# main.net
KiCad netlist of a schematic drawn in EAGLE
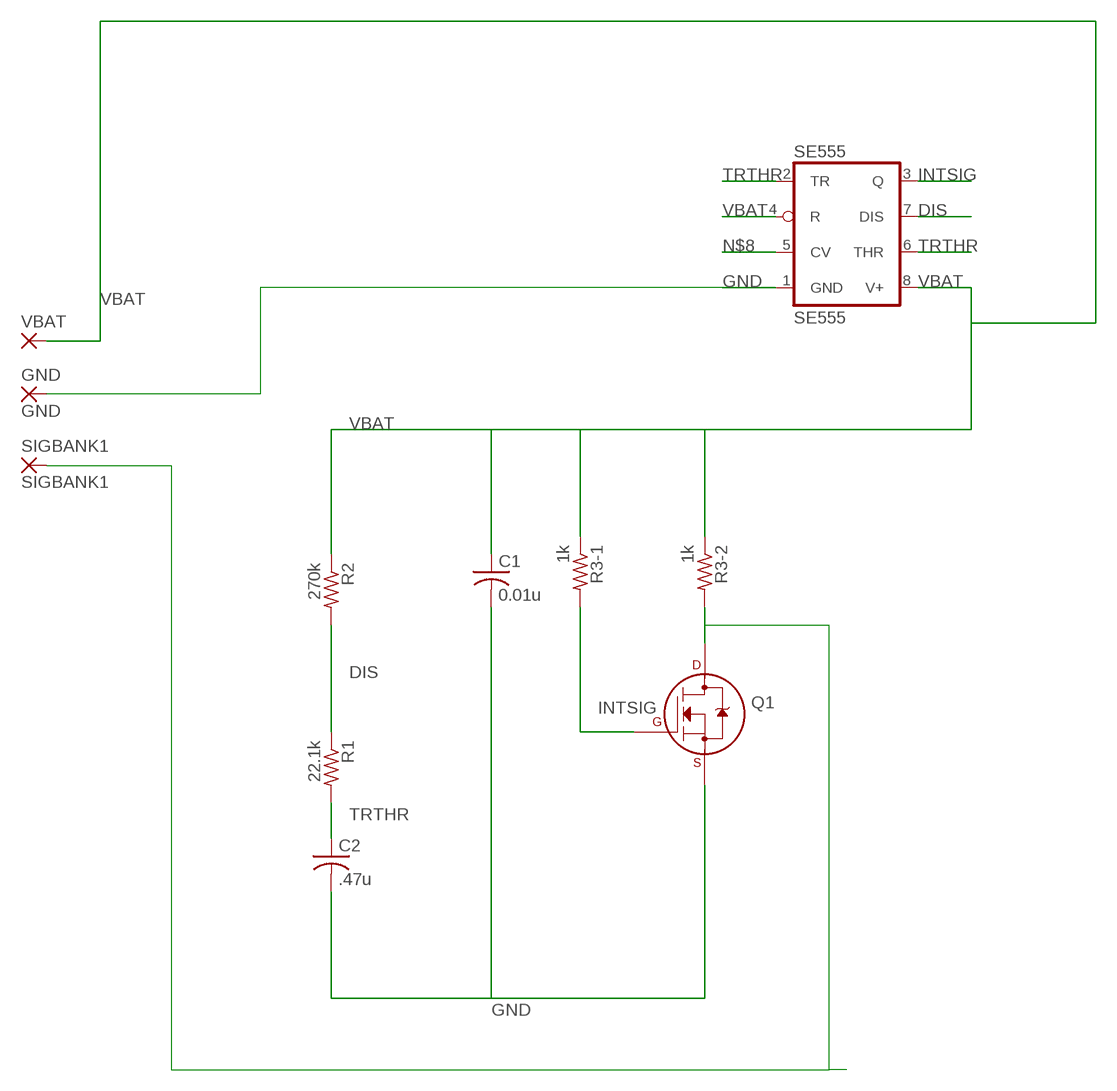
[diagram p0: schematic, sheet 1]

(export (version "E")
  (design (tool "Eeschema 10.0.6"))
  (components
    (comp (ref "C1")
      (value "0.01u")
      (footprint "eagle-import:C0805")
      (libsource (lib "eagle-import") (part "C-USC0805"))
    )
    (comp (ref "C2")
      (value ".47u")
      (footprint "eagle-import:C0805")
      (libsource (lib "eagle-import") (part "C-USC0805"))
    )
    (comp (ref "GND")
      (value "GND")
      (footprint "eagle-import:3,17_1,3")
      (libsource (lib "eagle-import") (part "3,17/1,3"))
    )
    (comp (ref "Q1")
      (value "2N7002_SOT23")
      (footprint "eagle-import:SOT-23")
      (libsource (lib "eagle-import") (part "2N700_SOT232"))
    )
    (comp (ref "R1")
      (value "22.1k")
      (footprint "eagle-import:R0805")
      (libsource (lib "eagle-import") (part "R-US_R0805"))
    )
    (comp (ref "R2")
      (value "270k")
      (footprint "eagle-import:R0805")
      (libsource (lib "eagle-import") (part "R-US_R0805"))
    )
    (comp (ref "R3-1")
      (value "1k")
      (footprint "eagle-import:R0805")
      (libsource (lib "eagle-import") (part "R-US_R0805"))
    )
    (comp (ref "R3-2")
      (value "1k")
      (footprint "eagle-import:R0805")
      (libsource (lib "eagle-import") (part "R-US_R0805"))
    )
    (comp (ref "SE555")
      (value "SE555")
      (footprint "eagle-import:SO08")
      (libsource (lib "eagle-import") (part "555DLM"))
    )
    (comp (ref "SIGBANK1")
      (value "SIGBANK1")
      (footprint "eagle-import:3,17_1,3")
      (libsource (lib "eagle-import") (part "3,17/1,3"))
    )
    (comp (ref "VBAT")
      (value "3,17/1,3")
      (footprint "eagle-import:3,17_1,3")
      (libsource (lib "eagle-import") (part "3,17/1,3"))
    )
  )
  (nets
    (net (code "1") (name "/DIS") (class "Default")
      (node (ref "R1") (pin "1") (pinfunction "1_1") (pintype "passive"))
      (node (ref "R2") (pin "2") (pinfunction "2_2") (pintype "passive"))
      (node (ref "SE555") (pin "7") (pinfunction "DIS_7") (pintype "input"))
    )
    (net (code "2") (name "/GND") (class "Default")
      (node (ref "C1") (pin "2") (pinfunction "2_2") (pintype "passive"))
      (node (ref "C2") (pin "2") (pinfunction "2_2") (pintype "passive"))
      (node (ref "GND") (pin "1") (pinfunction "P_1") (pintype "passive"))
      (node (ref "Q1") (pin "2") (pinfunction "S_2") (pintype "bidirectional"))
      (node (ref "SE555") (pin "1") (pinfunction "GND_1") (pintype "power_in"))
    )
    (net (code "3") (name "/INTSIG") (class "Default")
      (node (ref "Q1") (pin "1") (pinfunction "G_1") (pintype "tri_state"))
      (node (ref "R3-1") (pin "2") (pinfunction "2_2") (pintype "passive"))
      (node (ref "SE555") (pin "3") (pinfunction "Q_3") (pintype "output"))
    )
    (net (code "4") (name "/N$8") (class "Default")
      (node (ref "SE555") (pin "5") (pinfunction "CV_5") (pintype "input"))
    )
    (net (code "5") (name "/TRTHR") (class "Default")
      (node (ref "C2") (pin "1") (pinfunction "1_1") (pintype "passive"))
      (node (ref "R1") (pin "2") (pinfunction "2_2") (pintype "passive"))
      (node (ref "SE555") (pin "2") (pinfunction "TR_2") (pintype "input"))
      (node (ref "SE555") (pin "6") (pinfunction "THR_6") (pintype "input"))
    )
    (net (code "6") (name "/VBAT") (class "Default")
      (node (ref "C1") (pin "1") (pinfunction "1_1") (pintype "passive"))
      (node (ref "R2") (pin "1") (pinfunction "1_1") (pintype "passive"))
      (node (ref "R3-1") (pin "1") (pinfunction "1_1") (pintype "passive"))
      (node (ref "R3-2") (pin "1") (pinfunction "1_1") (pintype "passive"))
      (node (ref "SE555") (pin "4") (pinfunction "R_4") (pintype "input"))
      (node (ref "SE555") (pin "8") (pinfunction "V+_8") (pintype "power_in"))
      (node (ref "VBAT") (pin "1") (pinfunction "P_1") (pintype "passive"))
    )
    (net (code "7") (name "Net-(Q1-D)") (class "Default")
      (node (ref "Q1") (pin "3") (pinfunction "D_3") (pintype "bidirectional"))
      (node (ref "R3-2") (pin "2") (pinfunction "2_2") (pintype "passive"))
      (node (ref "SIGBANK1") (pin "1") (pinfunction "P_1") (pintype "passive"))
    )
  )
)
